# bldc-robot-main-mbed.net
KiCad netlist of a schematic drawn in Altium Designer
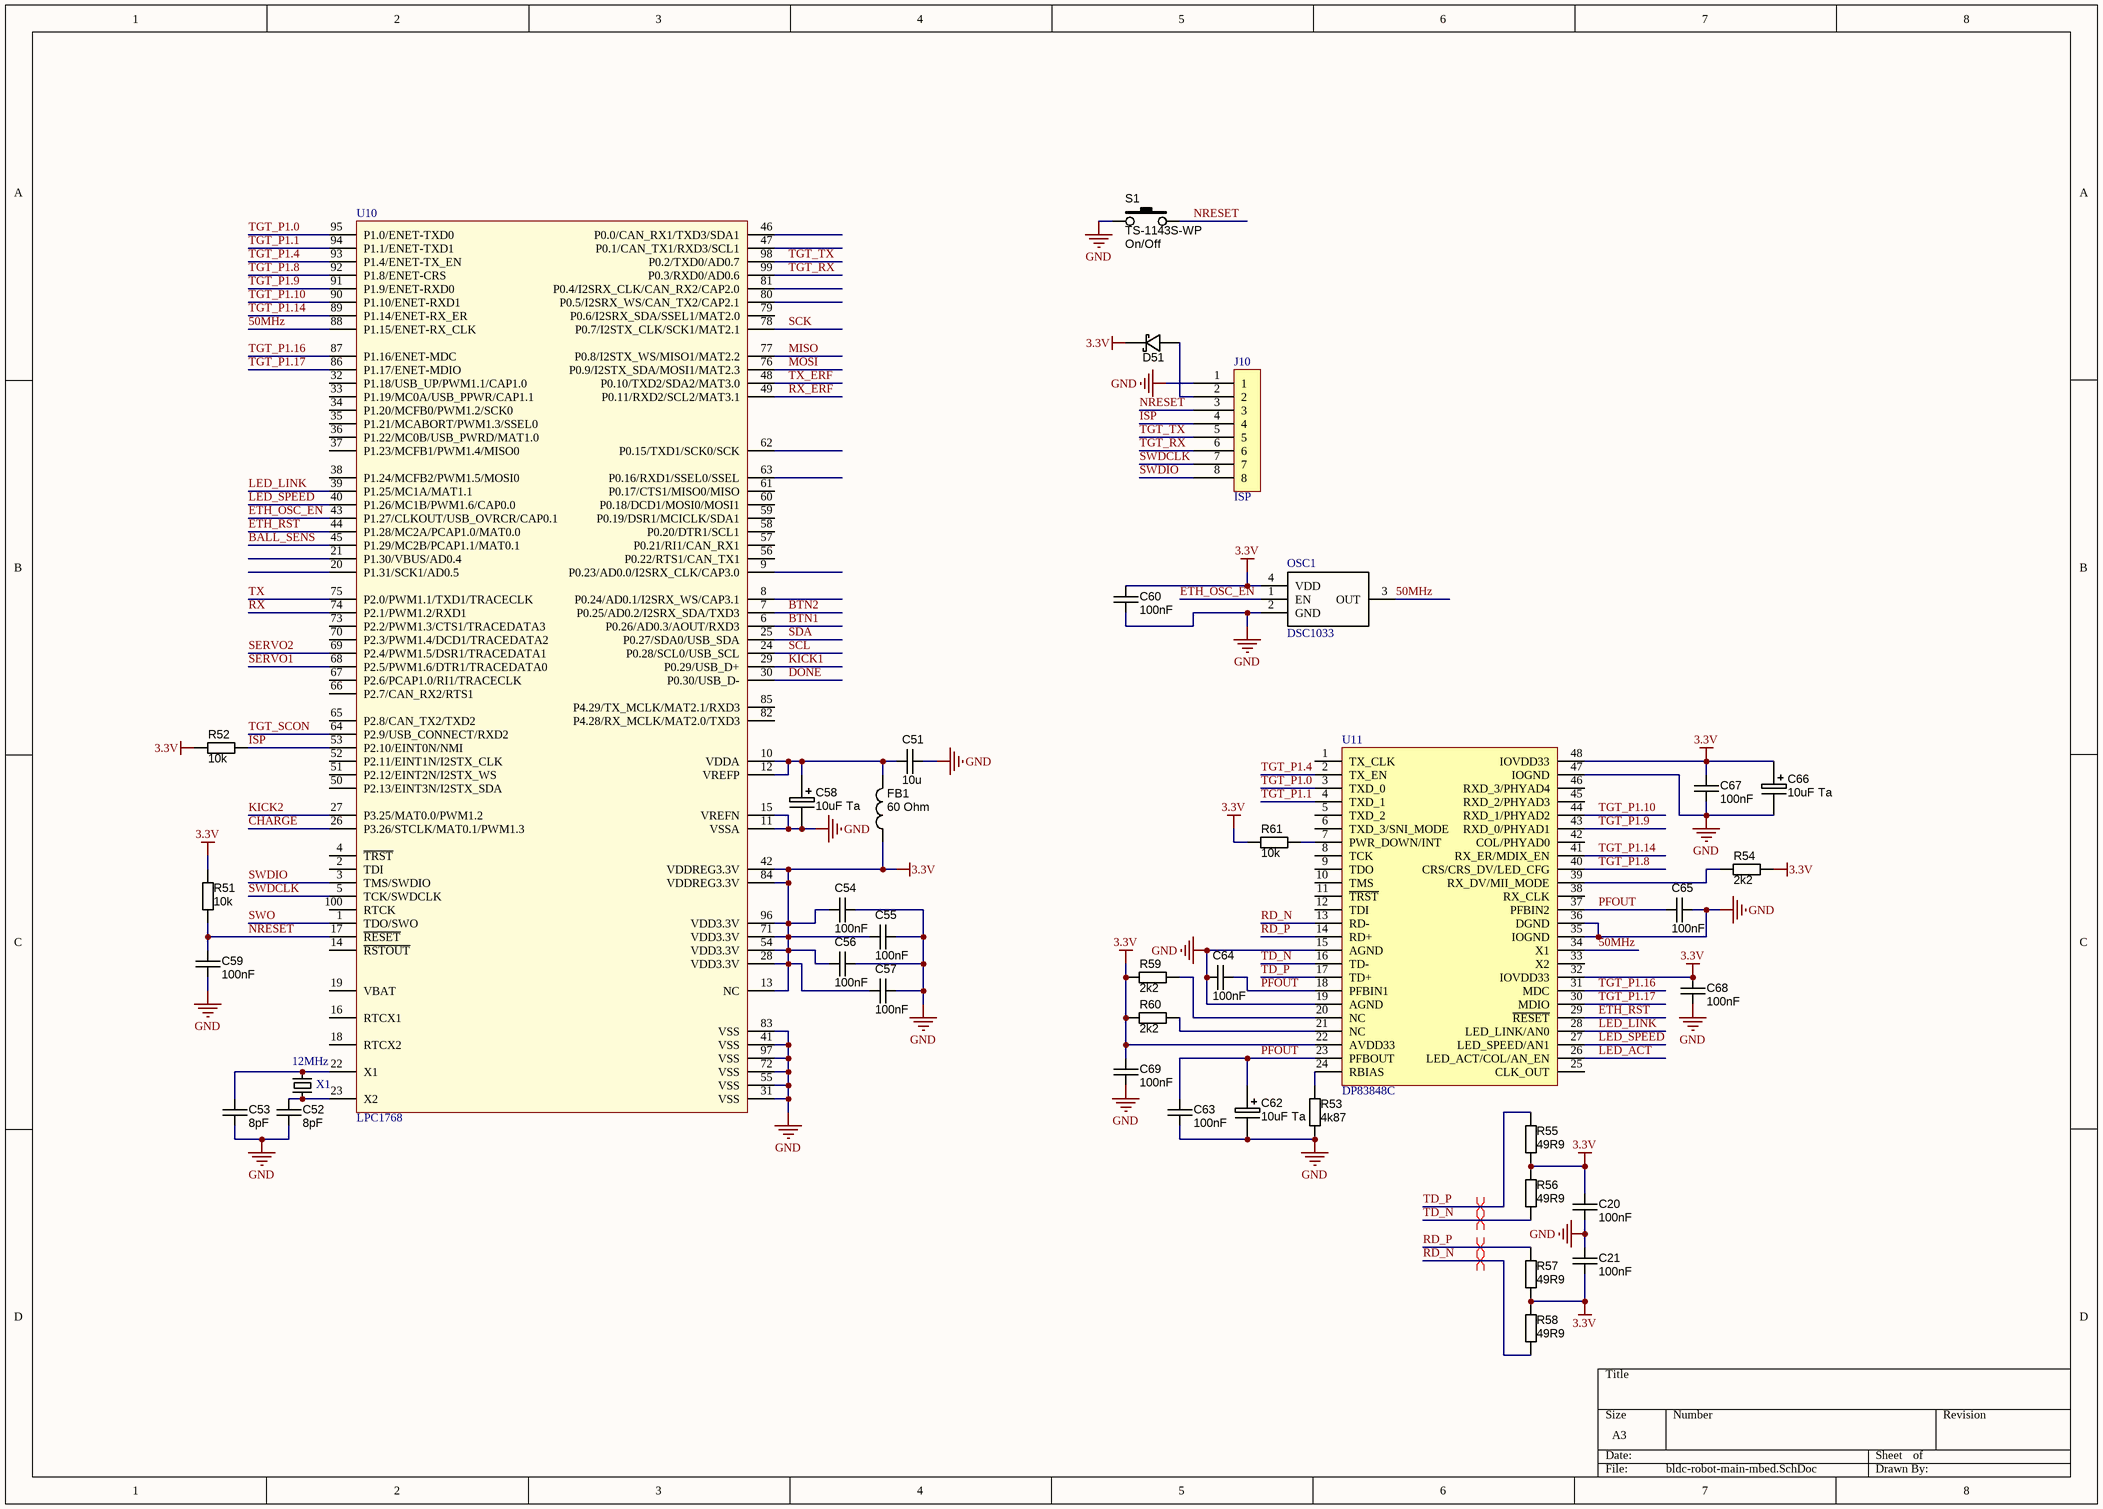
[diagram p0: bldc-robot-main-mbed.SchDoc]

(export (version "E")
  (design (tool "Eeschema 10.0.6"))
  (components
    (comp (ref "C20")
      (value "100nF")
      (footprint "CAPC1608X90N")
      (description "Capacitor SMD Cer 18pF 2% 100V NP0 0603")
      (fields (field (name "TOLERANCE") "±2%"))
      (libsource (lib "PBL - Capacitors") (part "CAPC_18p_0603_100V"))
    )
    (comp (ref "C21")
      (value "100nF")
      (footprint "CAPC1608X90N")
      (description "Capacitor SMD Cer 18pF 2% 100V NP0 0603")
      (fields (field (name "TOLERANCE") "±2%"))
      (libsource (lib "PBL - Capacitors") (part "CAPC_18p_0603_100V"))
    )
    (comp (ref "C51")
      (value "10u")
      (footprint "CAPC2012X135N")
      (description "Capacitor SMD Cer 10uF 10% 10V X5R 0805")
      (fields (field (name "TOLERANCE") "±10%"))
      (libsource (lib "PBL - Capacitors") (part "CAPC_10u_0805_10V"))
    )
    (comp (ref "C52")
      (value "8pF")
      (footprint "CAPC1608X90N")
      (description "Capacitor SMD Cer 18pF 2% 100V NP0 0603")
      (fields (field (name "TOLERANCE") "±2%"))
      (libsource (lib "PBL - Capacitors") (part "CAPC_18p_0603_100V"))
    )
    (comp (ref "C53")
      (value "8pF")
      (footprint "CAPC1608X90N")
      (description "Capacitor SMD Cer 18pF 2% 100V NP0 0603")
      (fields (field (name "TOLERANCE") "±2%"))
      (libsource (lib "PBL - Capacitors") (part "CAPC_18p_0603_100V"))
    )
    (comp (ref "C54")
      (value "100nF")
      (footprint "CAPC1608X90N")
      (description "Capacitor SMD Cer 18pF 2% 100V NP0 0603")
      (fields (field (name "TOLERANCE") "±2%"))
      (libsource (lib "PBL - Capacitors") (part "CAPC_18p_0603_100V"))
    )
    (comp (ref "C55")
      (value "100nF")
      (footprint "CAPC1608X90N")
      (description "Capacitor SMD Cer 18pF 2% 100V NP0 0603")
      (fields (field (name "TOLERANCE") "±2%"))
      (libsource (lib "PBL - Capacitors") (part "CAPC_18p_0603_100V"))
    )
    (comp (ref "C56")
      (value "100nF")
      (footprint "CAPC1608X90N")
      (description "Capacitor SMD Cer 18pF 2% 100V NP0 0603")
      (fields (field (name "TOLERANCE") "±2%"))
      (libsource (lib "PBL - Capacitors") (part "CAPC_18p_0603_100V"))
    )
    (comp (ref "C57")
      (value "100nF")
      (footprint "CAPC1608X90N")
      (description "Capacitor SMD Cer 18pF 2% 100V NP0 0603")
      (fields (field (name "TOLERANCE") "±2%"))
      (libsource (lib "PBL - Capacitors") (part "CAPC_18p_0603_100V"))
    )
    (comp (ref "C58")
      (value "10uF Ta")
      (footprint "CAPMP3528X210N")
      (description "Capacitor SMD Tantalum 47uF 20% 6.3V 1210")
      (fields (field (name "TOLERANCE") "±20%"))
      (libsource (lib "PBL - Capacitors") (part "CAPT_47u_1210_6V3"))
    )
    (comp (ref "C59")
      (value "100nF")
      (footprint "CAPC1608X90N")
      (description "Capacitor SMD Cer 18pF 2% 100V NP0 0603")
      (fields (field (name "TOLERANCE") "±2%"))
      (libsource (lib "PBL - Capacitors") (part "CAPC_18p_0603_100V"))
    )
    (comp (ref "C60")
      (value "100nF")
      (footprint "CAPC1608X90N")
      (description "Capacitor SMD Cer 18pF 2% 100V NP0 0603")
      (fields (field (name "TOLERANCE") "±2%"))
      (libsource (lib "PBL - Capacitors") (part "CAPC_18p_0603_100V"))
    )
    (comp (ref "C62")
      (value "10uF Ta")
      (footprint "CAPMP3528X210N")
      (description "Capacitor SMD Tantalum 47uF 20% 6.3V 1210")
      (fields (field (name "TOLERANCE") "±20%"))
      (libsource (lib "PBL - Capacitors") (part "CAPT_47u_1210_6V3"))
    )
    (comp (ref "C63")
      (value "100nF")
      (footprint "CAPC1608X90N")
      (description "Capacitor SMD Cer 18pF 2% 100V NP0 0603")
      (fields (field (name "TOLERANCE") "±2%"))
      (libsource (lib "PBL - Capacitors") (part "CAPC_18p_0603_100V"))
    )
    (comp (ref "C64")
      (value "100nF")
      (footprint "CAPC1608X90N")
      (description "Capacitor SMD Cer 18pF 2% 100V NP0 0603")
      (fields (field (name "TOLERANCE") "±2%"))
      (libsource (lib "PBL - Capacitors") (part "CAPC_18p_0603_100V"))
    )
    (comp (ref "C65")
      (value "100nF")
      (footprint "CAPC1608X90N")
      (description "Capacitor SMD Cer 18pF 2% 100V NP0 0603")
      (fields (field (name "TOLERANCE") "±2%"))
      (libsource (lib "PBL - Capacitors") (part "CAPC_18p_0603_100V"))
    )
    (comp (ref "C66")
      (value "10uF Ta")
      (footprint "CAPMP3528X210N")
      (description "Capacitor SMD Tantalum 47uF 20% 6.3V 1210")
      (fields (field (name "TOLERANCE") "±20%"))
      (libsource (lib "PBL - Capacitors") (part "CAPT_47u_1210_6V3"))
    )
    (comp (ref "C67")
      (value "100nF")
      (footprint "CAPC1608X90N")
      (description "Capacitor SMD Cer 18pF 2% 100V NP0 0603")
      (fields (field (name "TOLERANCE") "±2%"))
      (libsource (lib "PBL - Capacitors") (part "CAPC_18p_0603_100V"))
    )
    (comp (ref "C68")
      (value "100nF")
      (footprint "CAPC1608X90N")
      (description "Capacitor SMD Cer 18pF 2% 100V NP0 0603")
      (fields (field (name "TOLERANCE") "±2%"))
      (libsource (lib "PBL - Capacitors") (part "CAPC_18p_0603_100V"))
    )
    (comp (ref "C69")
      (value "100nF")
      (footprint "CAPC1608X90N")
      (description "Capacitor SMD Cer 18pF 2% 100V NP0 0603")
      (fields (field (name "TOLERANCE") "±2%"))
      (libsource (lib "PBL - Capacitors") (part "CAPC_18p_0603_100V"))
    )
    (comp (ref "D51")
      (value "~")
      (footprint "SOD323")
      (description "Diode Schottky SMD 20V 0.5A SOD123")
      (libsource (lib "PBL - Diodes") (part "DIODE_SCHOTTKY_SS0520"))
    )
    (comp (ref "FB1")
      (value "60 Ohm")
      (footprint "INDC1608N")
      (description "Ferrite bead 120 Ohm at 100 MHz 2A 0603 SMD")
      (libsource (lib "PBL - Inductors") (part "FERRITE_120R-100MHz_0603"))
    )
    (comp (ref "J10")
      (value "ISP")
      (footprint "MICRO-MATCH-8")
      (libsource (lib "connectors") (part "HEADER-8"))
    )
    (comp (ref "OSC1")
      (value "DSC1033")
      (footprint "DSC1033-3.2x2.5")
      (libsource (lib "misc") (part "DSC1033"))
    )
    (comp (ref "R51")
      (value "10k")
      (footprint "RESC1608X55N")
      (description "Resistor SMD chip 10k Ohm 0.1W 5% 0603")
      (fields (field (name "TOLERANCE") "±5%"))
      (libsource (lib "PBL - Resistors") (part "RES_10K_0603_5%"))
    )
    (comp (ref "R52")
      (value "10k")
      (footprint "RESC1608X55N")
      (description "Resistor SMD chip 10k Ohm 0.1W 5% 0603")
      (fields (field (name "TOLERANCE") "±5%"))
      (libsource (lib "") (part "RES_10K_0603_5%_1"))
    )
    (comp (ref "R53")
      (value "4k87")
      (footprint "RESC1608X55N")
      (description "Resistor SMD chip 10k Ohm 0.1W 5% 0603")
      (fields (field (name "TOLERANCE") "±5%"))
      (libsource (lib "PBL - Resistors") (part "RES_10K_0603_5%"))
    )
    (comp (ref "R54")
      (value "2k2")
      (footprint "RESC1608X55N")
      (description "Resistor SMD chip 10k Ohm 0.1W 5% 0603")
      (fields (field (name "TOLERANCE") "±5%"))
      (libsource (lib "") (part "RES_10K_0603_5%_1"))
    )
    (comp (ref "R55")
      (value "49R9")
      (footprint "RESC1608X55N")
      (description "Resistor SMD chip 10k Ohm 0.1W 5% 0603")
      (fields (field (name "TOLERANCE") "±5%"))
      (libsource (lib "PBL - Resistors") (part "RES_10K_0603_5%"))
    )
    (comp (ref "R56")
      (value "49R9")
      (footprint "RESC1608X55N")
      (description "Resistor SMD chip 10k Ohm 0.1W 5% 0603")
      (fields (field (name "TOLERANCE") "±5%"))
      (libsource (lib "PBL - Resistors") (part "RES_10K_0603_5%"))
    )
    (comp (ref "R57")
      (value "49R9")
      (footprint "RESC1608X55N")
      (description "Resistor SMD chip 10k Ohm 0.1W 5% 0603")
      (fields (field (name "TOLERANCE") "±5%"))
      (libsource (lib "PBL - Resistors") (part "RES_10K_0603_5%"))
    )
    (comp (ref "R58")
      (value "49R9")
      (footprint "RESC1608X55N")
      (description "Resistor SMD chip 10k Ohm 0.1W 5% 0603")
      (fields (field (name "TOLERANCE") "±5%"))
      (libsource (lib "PBL - Resistors") (part "RES_10K_0603_5%"))
    )
    (comp (ref "R59")
      (value "2k2")
      (footprint "RESC1608X55N")
      (description "Resistor SMD chip 10k Ohm 0.1W 5% 0603")
      (fields (field (name "TOLERANCE") "±5%"))
      (libsource (lib "") (part "RES_10K_0603_5%_1"))
    )
    (comp (ref "R60")
      (value "2k2")
      (footprint "RESC1608X55N")
      (description "Resistor SMD chip 10k Ohm 0.1W 5% 0603")
      (fields (field (name "TOLERANCE") "±5%"))
      (libsource (lib "") (part "RES_10K_0603_5%_1"))
    )
    (comp (ref "R61")
      (value "10k")
      (footprint "RESC1608X55N")
      (description "Resistor SMD chip 10k Ohm 0.1W 5% 0603")
      (fields (field (name "TOLERANCE") "±5%"))
      (libsource (lib "") (part "RES_10K_0603_5%_1"))
    )
    (comp (ref "S1")
      (value "TS-1143S-WP")
      (footprint "TS-1143S")
      (description "Switch SMD Tact 4.3mm Stem")
      (fields (field (name "FUNCTION") "On/Off"))
      (libsource (lib "PBL - Switches") (part "SW_SMD_PB_4.3mm"))
    )
    (comp (ref "U10") (value "LPC1768") (footprint "LQFP100") (libsource (lib "nxp") (part "LPC1768")))
    (comp (ref "U11")
      (value "DP83848C")
      (footprint "PQFP48")
      (libsource (lib "texas_instruments") (part "DP83848C"))
    )
    (comp (ref "X1")
      (value "12MHz")
      (footprint "XTAL-3.2x2.5")
      (libsource (lib "misc") (part "XTAL-3.2X2.5"))
    )
  )
  (nets
    (net (code "1") (name "/50MHz") (class "Default")
      (node (ref "OSC1") (pin "3") (pinfunction "OUT_3") (pintype "passive"))
      (node (ref "U10") (pin "88") (pinfunction "P1.15/ENET-RX_CLK_88") (pintype "passive"))
      (node (ref "U11") (pin "34") (pinfunction "X1_34") (pintype "passive"))
    )
    (net (code "2") (name "/BALL_SENS") (class "Default")
      (node (ref "U10") (pin "45") (pinfunction "P1.29/MC2B/PCAP1.1/MAT0.1_45") (pintype "passive"))
    )
    (net (code "3") (name "/BTN1") (class "Default")
      (node (ref "U10") (pin "6") (pinfunction "P0.26/AD0.3/AOUT/RXD3_6") (pintype "passive"))
    )
    (net (code "4") (name "/BTN2") (class "Default")
      (node (ref "U10") (pin "7") (pinfunction "P0.25/AD0.2/I2SRX_SDA/TXD3_7") (pintype "passive"))
    )
    (net (code "5") (name "/CHARGE") (class "Default")
      (node (ref "U10") (pin "26") (pinfunction "P3.26/STCLK/MAT0.1/PWM1.3_26") (pintype "passive"))
    )
    (net (code "6") (name "/DONE") (class "Default")
      (node (ref "U10") (pin "30") (pinfunction "P0.30/USB_D-_30") (pintype "passive"))
    )
    (net (code "7") (name "/ETH_OSC_EN") (class "Default")
      (node (ref "OSC1") (pin "1") (pinfunction "EN_1") (pintype "passive"))
      (node (ref "U10") (pin "43") (pinfunction "P1.27/CLKOUT/USB_OVRCR/CAP0.1_43") (pintype "passive"))
    )
    (net (code "8") (name "/ETH_RST") (class "Default")
      (node (ref "U10") (pin "44") (pinfunction "P1.28/MC2A/PCAP1.0/MAT0.0_44") (pintype "passive"))
      (node (ref "U11") (pin "29") (pinfunction "~{RESET}_29") (pintype "passive"))
    )
    (net (code "9") (name "/ISP") (class "Default")
      (node (ref "J10") (pin "4") (pinfunction "4_4") (pintype "passive"))
      (node (ref "R52") (pin "1") (pinfunction "1_1") (pintype "passive"))
      (node (ref "U10") (pin "53") (pinfunction "P2.10/EINT0N/NMI_53") (pintype "passive"))
    )
    (net (code "10") (name "/KICK1") (class "Default")
      (node (ref "U10") (pin "29") (pinfunction "P0.29/USB_D+_29") (pintype "passive"))
    )
    (net (code "11") (name "/KICK2") (class "Default")
      (node (ref "U10") (pin "27") (pinfunction "P3.25/MAT0.0/PWM1.2_27") (pintype "passive"))
    )
    (net (code "12") (name "/LED_ACT") (class "Default")
      (node (ref "U11") (pin "26") (pinfunction "LED_ACT/COL/AN_EN_26") (pintype "passive"))
    )
    (net (code "13") (name "/LED_LINK") (class "Default")
      (node (ref "U10") (pin "39") (pinfunction "P1.25/MC1A/MAT1.1_39") (pintype "passive"))
      (node (ref "U11") (pin "28") (pinfunction "LED_LINK/AN0_28") (pintype "passive"))
    )
    (net (code "14") (name "/LED_SPEED") (class "Default")
      (node (ref "U10") (pin "40") (pinfunction "P1.26/MC1B/PWM1.6/CAP0.0_40") (pintype "passive"))
      (node (ref "U11") (pin "27") (pinfunction "LED_SPEED/AN1_27") (pintype "passive"))
    )
    (net (code "15") (name "/MISO") (class "Default")
      (node (ref "U10") (pin "77") (pinfunction "P0.8/I2STX_WS/MISO1/MAT2.2_77") (pintype "passive"))
    )
    (net (code "16") (name "/MOSI") (class "Default")
      (node (ref "U10") (pin "76") (pinfunction "P0.9/I2STX_SDA/MOSI1/MAT2.3_76") (pintype "passive"))
    )
    (net (code "17") (name "/NRESET") (class "Default")
      (node (ref "C59") (pin "1") (pintype "passive"))
      (node (ref "J10") (pin "3") (pinfunction "3_3") (pintype "passive"))
      (node (ref "R51") (pin "2") (pinfunction "2_2") (pintype "passive"))
      (node (ref "S1") (pin "2") (pintype "passive"))
      (node (ref "U10") (pin "17") (pinfunction "~{RESET}_17") (pintype "passive"))
    )
    (net (code "18") (name "/PFOUT") (class "Default")
      (node (ref "C62") (pin "1") (pintype "passive"))
      (node (ref "C63") (pin "2") (pintype "passive"))
      (node (ref "C64") (pin "2") (pintype "passive"))
      (node (ref "C65") (pin "1") (pintype "passive"))
      (node (ref "U11") (pin "18") (pinfunction "PFBIN1_18") (pintype "passive"))
      (node (ref "U11") (pin "23") (pinfunction "PFBOUT_23") (pintype "passive"))
      (node (ref "U11") (pin "37") (pinfunction "PFBIN2_37") (pintype "passive"))
    )
    (net (code "19") (name "/RD_N") (class "Default")
      (node (ref "R58") (pin "2") (pinfunction "2_2") (pintype "passive"))
      (node (ref "U11") (pin "13") (pinfunction "RD-_13") (pintype "passive"))
    )
    (net (code "20") (name "/RD_P") (class "Default")
      (node (ref "R57") (pin "1") (pinfunction "1_1") (pintype "passive"))
      (node (ref "U11") (pin "14") (pinfunction "RD+_14") (pintype "passive"))
    )
    (net (code "21") (name "/RX") (class "Default")
      (node (ref "U10") (pin "74") (pinfunction "P2.1/PWM1.2/RXD1_74") (pintype "passive"))
    )
    (net (code "22") (name "/RX_ERF") (class "Default")
      (node (ref "U10") (pin "49") (pinfunction "P0.11/RXD2/SCL2/MAT3.1_49") (pintype "passive"))
    )
    (net (code "23") (name "/SCK") (class "Default")
      (node (ref "U10") (pin "78") (pinfunction "P0.7/I2STX_CLK/SCK1/MAT2.1_78") (pintype "passive"))
    )
    (net (code "24") (name "/SCL") (class "Default")
      (node (ref "U10") (pin "24") (pinfunction "P0.28/SCL0/USB_SCL_24") (pintype "passive"))
    )
    (net (code "25") (name "/SDA") (class "Default")
      (node (ref "U10") (pin "25") (pinfunction "P0.27/SDA0/USB_SDA_25") (pintype "passive"))
    )
    (net (code "26") (name "/SERVO1") (class "Default")
      (node (ref "U10") (pin "68") (pinfunction "P2.5/PWM1.6/DTR1/TRACEDATA0_68") (pintype "passive"))
    )
    (net (code "27") (name "/SERVO2") (class "Default")
      (node (ref "U10") (pin "69") (pinfunction "P2.4/PWM1.5/DSR1/TRACEDATA1_69") (pintype "passive"))
    )
    (net (code "28") (name "/SWDCLK") (class "Default")
      (node (ref "J10") (pin "7") (pinfunction "7_7") (pintype "passive"))
      (node (ref "U10") (pin "5") (pinfunction "TCK/SWDCLK_5") (pintype "passive"))
    )
    (net (code "29") (name "/SWDIO") (class "Default")
      (node (ref "J10") (pin "8") (pinfunction "8_8") (pintype "passive"))
      (node (ref "U10") (pin "3") (pinfunction "TMS/SWDIO_3") (pintype "passive"))
    )
    (net (code "30") (name "/SWO") (class "Default")
      (node (ref "U10") (pin "1") (pinfunction "TDO/SWO_1") (pintype "passive"))
    )
    (net (code "31") (name "/TD_N") (class "Default")
      (node (ref "R56") (pin "2") (pinfunction "2_2") (pintype "passive"))
      (node (ref "U11") (pin "16") (pinfunction "TD-_16") (pintype "passive"))
    )
    (net (code "32") (name "/TD_P") (class "Default")
      (node (ref "R55") (pin "1") (pinfunction "1_1") (pintype "passive"))
      (node (ref "U11") (pin "17") (pinfunction "TD+_17") (pintype "passive"))
    )
    (net (code "33") (name "/TGT_P1.0") (class "Default")
      (node (ref "U10") (pin "95") (pinfunction "P1.0/ENET-TXD0_95") (pintype "passive"))
      (node (ref "U11") (pin "3") (pinfunction "TXD_0_3") (pintype "passive"))
    )
    (net (code "34") (name "/TGT_P1.1") (class "Default")
      (node (ref "U10") (pin "94") (pinfunction "P1.1/ENET-TXD1_94") (pintype "passive"))
      (node (ref "U11") (pin "4") (pinfunction "TXD_1_4") (pintype "passive"))
    )
    (net (code "35") (name "/TGT_P1.4") (class "Default")
      (node (ref "U10") (pin "93") (pinfunction "P1.4/ENET-TX_EN_93") (pintype "passive"))
      (node (ref "U11") (pin "2") (pinfunction "TX_EN_2") (pintype "passive"))
    )
    (net (code "36") (name "/TGT_P1.8") (class "Default")
      (node (ref "U10") (pin "92") (pinfunction "P1.8/ENET-CRS_92") (pintype "passive"))
      (node (ref "U11") (pin "40") (pinfunction "CRS/CRS_DV/LED_CFG_40") (pintype "passive"))
    )
    (net (code "37") (name "/TGT_P1.9") (class "Default")
      (node (ref "U10") (pin "91") (pinfunction "P1.9/ENET-RXD0_91") (pintype "passive"))
      (node (ref "U11") (pin "43") (pinfunction "RXD_0/PHYAD1_43") (pintype "passive"))
    )
    (net (code "38") (name "/TGT_P1.10") (class "Default")
      (node (ref "U10") (pin "90") (pinfunction "P1.10/ENET-RXD1_90") (pintype "passive"))
      (node (ref "U11") (pin "44") (pinfunction "RXD_1/PHYAD2_44") (pintype "passive"))
    )
    (net (code "39") (name "/TGT_P1.14") (class "Default")
      (node (ref "U10") (pin "89") (pinfunction "P1.14/ENET-RX_ER_89") (pintype "passive"))
      (node (ref "U11") (pin "41") (pinfunction "RX_ER/MDIX_EN_41") (pintype "passive"))
    )
    (net (code "40") (name "/TGT_P1.16") (class "Default")
      (node (ref "U10") (pin "87") (pinfunction "P1.16/ENET-MDC_87") (pintype "passive"))
      (node (ref "U11") (pin "31") (pinfunction "MDC_31") (pintype "passive"))
    )
    (net (code "41") (name "/TGT_P1.17") (class "Default")
      (node (ref "U10") (pin "86") (pinfunction "P1.17/ENET-MDIO_86") (pintype "passive"))
      (node (ref "U11") (pin "30") (pinfunction "MDIO_30") (pintype "passive"))
    )
    (net (code "42") (name "/TGT_RX") (class "Default")
      (node (ref "J10") (pin "6") (pinfunction "6_6") (pintype "passive"))
      (node (ref "U10") (pin "99") (pinfunction "P0.3/RXD0/AD0.6_99") (pintype "passive"))
    )
    (net (code "43") (name "/TGT_SCON") (class "Default")
      (node (ref "U10") (pin "64") (pinfunction "P2.9/USB_CONNECT/RXD2_64") (pintype "passive"))
    )
    (net (code "44") (name "/TGT_TX") (class "Default")
      (node (ref "J10") (pin "5") (pinfunction "5_5") (pintype "passive"))
      (node (ref "U10") (pin "98") (pinfunction "P0.2/TXD0/AD0.7_98") (pintype "passive"))
    )
    (net (code "45") (name "/TX") (class "Default")
      (node (ref "U10") (pin "75") (pinfunction "P2.0/PWM1.1/TXD1/TRACECLK_75") (pintype "passive"))
    )
    (net (code "46") (name "/TX_ERF") (class "Default")
      (node (ref "U10") (pin "48") (pinfunction "P0.10/TXD2/SDA2/MAT3.0_48") (pintype "passive"))
    )
    (net (code "47") (name "3.3V") (class "Default")
      (node (ref "C20") (pin "2") (pintype "passive"))
      (node (ref "C21") (pin "1") (pintype "passive"))
      (node (ref "C54") (pin "1") (pintype "passive"))
      (node (ref "C55") (pin "1") (pintype "passive"))
      (node (ref "C56") (pin "1") (pintype "passive"))
      (node (ref "C57") (pin "1") (pintype "passive"))
      (node (ref "C60") (pin "2") (pintype "passive"))
      (node (ref "C66") (pin "1") (pintype "passive"))
      (node (ref "C67") (pin "2") (pintype "passive"))
      (node (ref "C68") (pin "2") (pintype "passive"))
      (node (ref "C69") (pin "2") (pintype "passive"))
      (node (ref "D51") (pin "K") (pinfunction "K_K") (pintype "passive"))
      (node (ref "FB1") (pin "1") (pinfunction "1_1") (pintype "passive"))
      (node (ref "OSC1") (pin "4") (pinfunction "VDD_4") (pintype "passive"))
      (node (ref "R51") (pin "1") (pinfunction "1_1") (pintype "passive"))
      (node (ref "R52") (pin "2") (pinfunction "2_2") (pintype "passive"))
      (node (ref "R54") (pin "1") (pinfunction "1_1") (pintype "passive"))
      (node (ref "R55") (pin "2") (pinfunction "2_2") (pintype "passive"))
      (node (ref "R56") (pin "1") (pinfunction "1_1") (pintype "passive"))
      (node (ref "R57") (pin "2") (pinfunction "2_2") (pintype "passive"))
      (node (ref "R58") (pin "1") (pinfunction "1_1") (pintype "passive"))
      (node (ref "R59") (pin "2") (pinfunction "2_2") (pintype "passive"))
      (node (ref "R60") (pin "2") (pinfunction "2_2") (pintype "passive"))
      (node (ref "R61") (pin "2") (pinfunction "2_2") (pintype "passive"))
      (node (ref "U10") (pin "13") (pinfunction "NC_13") (pintype "passive"))
      (node (ref "U10") (pin "28") (pinfunction "VDD3.3V_28") (pintype "passive"))
      (node (ref "U10") (pin "42") (pinfunction "VDDREG3.3V_42") (pintype "passive"))
      (node (ref "U10") (pin "54") (pinfunction "VDD3.3V_54") (pintype "passive"))
      (node (ref "U10") (pin "71") (pinfunction "VDD3.3V_71") (pintype "passive"))
      (node (ref "U10") (pin "84") (pinfunction "VDDREG3.3V_84") (pintype "passive"))
      (node (ref "U10") (pin "96") (pinfunction "VDD3.3V_96") (pintype "passive"))
      (node (ref "U11") (pin "22") (pinfunction "AVDD33_22") (pintype "passive"))
      (node (ref "U11") (pin "32") (pinfunction "IOVDD33_32") (pintype "passive"))
      (node (ref "U11") (pin "48") (pinfunction "IOVDD33_48") (pintype "passive"))
    )
    (net (code "48") (name "GND") (class "Default")
      (node (ref "C20") (pin "1") (pintype "passive"))
      (node (ref "C21") (pin "2") (pintype "passive"))
      (node (ref "C51") (pin "2") (pintype "passive"))
      (node (ref "C52") (pin "2") (pintype "passive"))
      (node (ref "C53") (pin "2") (pintype "passive"))
      (node (ref "C54") (pin "2") (pintype "passive"))
      (node (ref "C55") (pin "2") (pintype "passive"))
      (node (ref "C56") (pin "2") (pintype "passive"))
      (node (ref "C57") (pin "2") (pintype "passive"))
      (node (ref "C58") (pin "2") (pintype "passive"))
      (node (ref "C59") (pin "2") (pintype "passive"))
      (node (ref "C60") (pin "1") (pintype "passive"))
      (node (ref "C62") (pin "2") (pintype "passive"))
      (node (ref "C63") (pin "1") (pintype "passive"))
      (node (ref "C64") (pin "1") (pintype "passive"))
      (node (ref "C65") (pin "2") (pintype "passive"))
      (node (ref "C66") (pin "2") (pintype "passive"))
      (node (ref "C67") (pin "1") (pintype "passive"))
      (node (ref "C68") (pin "1") (pintype "passive"))
      (node (ref "C69") (pin "1") (pintype "passive"))
      (node (ref "J10") (pin "1") (pinfunction "1_1") (pintype "passive"))
      (node (ref "OSC1") (pin "2") (pinfunction "GND_2") (pintype "passive"))
      (node (ref "R53") (pin "2") (pinfunction "2_2") (pintype "passive"))
      (node (ref "S1") (pin "1") (pintype "passive"))
      (node (ref "U10") (pin "11") (pinfunction "VSSA_11") (pintype "passive"))
      (node (ref "U10") (pin "15") (pinfunction "VREFN_15") (pintype "passive"))
      (node (ref "U10") (pin "31") (pinfunction "VSS_31") (pintype "passive"))
      (node (ref "U10") (pin "41") (pinfunction "VSS_41") (pintype "passive"))
      (node (ref "U10") (pin "55") (pinfunction "VSS_55") (pintype "passive"))
      (node (ref "U10") (pin "72") (pinfunction "VSS_72") (pintype "passive"))
      (node (ref "U10") (pin "83") (pinfunction "VSS_83") (pintype "passive"))
      (node (ref "U10") (pin "97") (pinfunction "VSS_97") (pintype "passive"))
      (node (ref "U11") (pin "15") (pinfunction "AGND_15") (pintype "passive"))
      (node (ref "U11") (pin "19") (pinfunction "AGND_19") (pintype "passive"))
      (node (ref "U11") (pin "35") (pinfunction "IOGND_35") (pintype "passive"))
      (node (ref "U11") (pin "36") (pinfunction "DGND_36") (pintype "passive"))
      (node (ref "U11") (pin "47") (pinfunction "IOGND_47") (pintype "passive"))
    )
    (net (code "49") (name "Net-(D51-PadA)") (class "Default")
      (node (ref "D51") (pin "A") (pinfunction "A_A") (pintype "passive"))
      (node (ref "J10") (pin "2") (pinfunction "2_2") (pintype "passive"))
    )
    (net (code "50") (name "Net-(R59-Pad1)") (class "Default")
      (node (ref "R59") (pin "1") (pinfunction "1_1") (pintype "passive"))
      (node (ref "U11") (pin "20") (pinfunction "NC_20") (pintype "passive"))
    )
    (net (code "51") (name "Net-(R60-Pad1)") (class "Default")
      (node (ref "R60") (pin "1") (pinfunction "1_1") (pintype "passive"))
      (node (ref "U11") (pin "21") (pinfunction "NC_21") (pintype "passive"))
    )
    (net (code "52") (name "Net-(U10-VDDA)") (class "Default")
      (node (ref "C51") (pin "1") (pintype "passive"))
      (node (ref "C58") (pin "1") (pintype "passive"))
      (node (ref "FB1") (pin "2") (pinfunction "2_2") (pintype "passive"))
      (node (ref "U10") (pin "10") (pinfunction "VDDA_10") (pintype "passive"))
      (node (ref "U10") (pin "12") (pinfunction "VREFP_12") (pintype "passive"))
    )
    (net (code "53") (name "Net-(U10-X1)") (class "Default")
      (node (ref "C53") (pin "1") (pintype "passive"))
      (node (ref "U10") (pin "22") (pinfunction "X1_22") (pintype "passive"))
      (node (ref "X1") (pin "3") (pinfunction "3_3") (pintype "passive"))
    )
    (net (code "54") (name "Net-(U10-X2)") (class "Default")
      (node (ref "C52") (pin "1") (pintype "passive"))
      (node (ref "U10") (pin "23") (pinfunction "X2_23") (pintype "passive"))
      (node (ref "X1") (pin "1") (pinfunction "1_1") (pintype "passive"))
    )
    (net (code "55") (name "Net-(U11-PWR_DOWN{slash}INT)") (class "Default")
      (node (ref "R61") (pin "1") (pinfunction "1_1") (pintype "passive"))
      (node (ref "U11") (pin "7") (pinfunction "PWR_DOWN/INT_7") (pintype "passive"))
    )
    (net (code "56") (name "Net-(U11-RBIAS)") (class "Default")
      (node (ref "R53") (pin "1") (pinfunction "1_1") (pintype "passive"))
      (node (ref "U11") (pin "24") (pinfunction "RBIAS_24") (pintype "passive"))
    )
    (net (code "57") (name "Net-(U11-RX_DV{slash}MII_MODE)") (class "Default")
      (node (ref "R54") (pin "2") (pinfunction "2_2") (pintype "passive"))
      (node (ref "U11") (pin "39") (pinfunction "RX_DV/MII_MODE_39") (pintype "passive"))
    )
    (net (code "58") (name "unconnected-(U10-P0.0{slash}CAN_RX1{slash}TXD3{slash}SDA1-Pad46)") (class "Default")
      (node (ref "U10") (pin "46") (pinfunction "P0.0/CAN_RX1/TXD3/SDA1_46") (pintype "passive"))
    )
    (net (code "59") (name "unconnected-(U10-P0.1{slash}CAN_TX1{slash}RXD3{slash}SCL1-Pad47)") (class "Default")
      (node (ref "U10") (pin "47") (pinfunction "P0.1/CAN_TX1/RXD3/SCL1_47") (pintype "passive"))
    )
    (net (code "60") (name "unconnected-(U10-P0.4{slash}I2SRX_CLK{slash}CAN_RX2{slash}CAP2.0-Pad81)") (class "Default")
      (node (ref "U10") (pin "81") (pinfunction "P0.4/I2SRX_CLK/CAN_RX2/CAP2.0_81") (pintype "passive"))
    )
    (net (code "61") (name "unconnected-(U10-P0.5{slash}I2SRX_WS{slash}CAN_TX2{slash}CAP2.1-Pad80)") (class "Default")
      (node (ref "U10") (pin "80") (pinfunction "P0.5/I2SRX_WS/CAN_TX2/CAP2.1_80") (pintype "passive"))
    )
    (net (code "62") (name "unconnected-(U10-P0.6{slash}I2SRX_SDA{slash}SSEL1{slash}MAT2.0-Pad79)") (class "Default")
      (node (ref "U10") (pin "79") (pinfunction "P0.6/I2SRX_SDA/SSEL1/MAT2.0_79") (pintype "passive"))
    )
    (net (code "63") (name "unconnected-(U10-P0.15{slash}TXD1{slash}SCK0{slash}SCK-Pad62)") (class "Default")
      (node (ref "U10") (pin "62") (pinfunction "P0.15/TXD1/SCK0/SCK_62") (pintype "passive"))
    )
    (net (code "64") (name "unconnected-(U10-P0.16{slash}RXD1{slash}SSEL0{slash}SSEL-Pad63)") (class "Default")
      (node (ref "U10") (pin "63") (pinfunction "P0.16/RXD1/SSEL0/SSEL_63") (pintype "passive"))
    )
    (net (code "65") (name "unconnected-(U10-P0.17{slash}CTS1{slash}MISO0{slash}MISO-Pad61)") (class "Default")
      (node (ref "U10") (pin "61") (pinfunction "P0.17/CTS1/MISO0/MISO_61") (pintype "passive"))
    )
    (net (code "66") (name "unconnected-(U10-P0.18{slash}DCD1{slash}MOSI0{slash}MOSI1-Pad60)") (class "Default")
      (node (ref "U10") (pin "60") (pinfunction "P0.18/DCD1/MOSI0/MOSI1_60") (pintype "passive"))
    )
    (net (code "67") (name "unconnected-(U10-P0.19{slash}DSR1{slash}MCICLK{slash}SDA1-Pad59)") (class "Default")
      (node (ref "U10") (pin "59") (pinfunction "P0.19/DSR1/MCICLK/SDA1_59") (pintype "passive"))
    )
    (net (code "68") (name "unconnected-(U10-P0.20{slash}DTR1{slash}SCL1-Pad58)") (class "Default")
      (node (ref "U10") (pin "58") (pinfunction "P0.20/DTR1/SCL1_58") (pintype "passive"))
    )
    (net (code "69") (name "unconnected-(U10-P0.21{slash}RI1{slash}CAN_RX1-Pad57)") (class "Default")
      (node (ref "U10") (pin "57") (pinfunction "P0.21/RI1/CAN_RX1_57") (pintype "passive"))
    )
    (net (code "70") (name "unconnected-(U10-P0.22{slash}RTS1{slash}CAN_TX1-Pad56)") (class "Default")
      (node (ref "U10") (pin "56") (pinfunction "P0.22/RTS1/CAN_TX1_56") (pintype "passive"))
    )
    (net (code "71") (name "unconnected-(U10-P0.23{slash}AD0.0{slash}I2SRX_CLK{slash}CAP3.0-Pad9)") (class "Default")
      (node (ref "U10") (pin "9") (pinfunction "P0.23/AD0.0/I2SRX_CLK/CAP3.0_9") (pintype "passive"))
    )
    (net (code "72") (name "unconnected-(U10-P0.24{slash}AD0.1{slash}I2SRX_WS{slash}CAP3.1-Pad8)") (class "Default")
      (node (ref "U10") (pin "8") (pinfunction "P0.24/AD0.1/I2SRX_WS/CAP3.1_8") (pintype "passive"))
    )
    (net (code "73") (name "unconnected-(U10-P1.18{slash}USB_UP{slash}PWM1.1{slash}CAP1.0-Pad32)") (class "Default")
      (node (ref "U10") (pin "32") (pinfunction "P1.18/USB_UP/PWM1.1/CAP1.0_32") (pintype "passive"))
    )
    (net (code "74") (name "unconnected-(U10-P1.19{slash}MC0A{slash}USB_PPWR{slash}CAP1.1-Pad33)") (class "Default")
      (node (ref "U10") (pin "33") (pinfunction "P1.19/MC0A/USB_PPWR/CAP1.1_33") (pintype "passive"))
    )
    (net (code "75") (name "unconnected-(U10-P1.20{slash}MCFB0{slash}PWM1.2{slash}SCK0-Pad34)") (class "Default")
      (node (ref "U10") (pin "34") (pinfunction "P1.20/MCFB0/PWM1.2/SCK0_34") (pintype "passive"))
    )
    (net (code "76") (name "unconnected-(U10-P1.21{slash}MCABORT{slash}PWM1.3{slash}SSEL0-Pad35)") (class "Default")
      (node (ref "U10") (pin "35") (pinfunction "P1.21/MCABORT/PWM1.3/SSEL0_35") (pintype "passive"))
    )
    (net (code "77") (name "unconnected-(U10-P1.22{slash}MC0B{slash}USB_PWRD{slash}MAT1.0-Pad36)") (class "Default")
      (node (ref "U10") (pin "36") (pinfunction "P1.22/MC0B/USB_PWRD/MAT1.0_36") (pintype "passive"))
    )
    (net (code "78") (name "unconnected-(U10-P1.23{slash}MCFB1{slash}PWM1.4{slash}MISO0-Pad37)") (class "Default")
      (node (ref "U10") (pin "37") (pinfunction "P1.23/MCFB1/PWM1.4/MISO0_37") (pintype "passive"))
    )
    (net (code "79") (name "unconnected-(U10-P1.24{slash}MCFB2{slash}PWM1.5{slash}MOSI0-Pad38)") (class "Default")
      (node (ref "U10") (pin "38") (pinfunction "P1.24/MCFB2/PWM1.5/MOSI0_38") (pintype "passive"))
    )
    (net (code "80") (name "unconnected-(U10-P1.30{slash}VBUS{slash}AD0.4-Pad21)") (class "Default")
      (node (ref "U10") (pin "21") (pinfunction "P1.30/VBUS/AD0.4_21") (pintype "passive"))
    )
    (net (code "81") (name "unconnected-(U10-P1.31{slash}SCK1{slash}AD0.5-Pad20)") (class "Default")
      (node (ref "U10") (pin "20") (pinfunction "P1.31/SCK1/AD0.5_20") (pintype "passive"))
    )
    (net (code "82") (name "unconnected-(U10-P2.2{slash}PWM1.3{slash}CTS1{slash}TRACEDATA3-Pad73)") (class "Default")
      (node (ref "U10") (pin "73") (pinfunction "P2.2/PWM1.3/CTS1/TRACEDATA3_73") (pintype "passive"))
    )
    (net (code "83") (name "unconnected-(U10-P2.3{slash}PWM1.4{slash}DCD1{slash}TRACEDATA2-Pad70)") (class "Default")
      (node (ref "U10") (pin "70") (pinfunction "P2.3/PWM1.4/DCD1/TRACEDATA2_70") (pintype "passive"))
    )
    (net (code "84") (name "unconnected-(U10-P2.6{slash}PCAP1.0{slash}RI1{slash}TRACECLK-Pad67)") (class "Default")
      (node (ref "U10") (pin "67") (pinfunction "P2.6/PCAP1.0/RI1/TRACECLK_67") (pintype "passive"))
    )
    (net (code "85") (name "unconnected-(U10-P2.7{slash}CAN_RX2{slash}RTS1-Pad66)") (class "Default")
      (node (ref "U10") (pin "66") (pinfunction "P2.7/CAN_RX2/RTS1_66") (pintype "passive"))
    )
    (net (code "86") (name "unconnected-(U10-P2.8{slash}CAN_TX2{slash}TXD2-Pad65)") (class "Default")
      (node (ref "U10") (pin "65") (pinfunction "P2.8/CAN_TX2/TXD2_65") (pintype "passive"))
    )
    (net (code "87") (name "unconnected-(U10-P2.11{slash}EINT1N{slash}I2STX_CLK-Pad52)") (class "Default")
      (node (ref "U10") (pin "52") (pinfunction "P2.11/EINT1N/I2STX_CLK_52") (pintype "passive"))
    )
    (net (code "88") (name "unconnected-(U10-P2.12{slash}EINT2N{slash}I2STX_WS-Pad51)") (class "Default")
      (node (ref "U10") (pin "51") (pinfunction "P2.12/EINT2N/I2STX_WS_51") (pintype "passive"))
    )
    (net (code "89") (name "unconnected-(U10-P2.13{slash}EINT3N{slash}I2STX_SDA-Pad50)") (class "Default")
      (node (ref "U10") (pin "50") (pinfunction "P2.13/EINT3N/I2STX_SDA_50") (pintype "passive"))
    )
    (net (code "90") (name "unconnected-(U10-P4.28{slash}RX_MCLK{slash}MAT2.0{slash}TXD3-Pad82)") (class "Default")
      (node (ref "U10") (pin "82") (pinfunction "P4.28/RX_MCLK/MAT2.0/TXD3_82") (pintype "passive"))
    )
    (net (code "91") (name "unconnected-(U10-P4.29{slash}TX_MCLK{slash}MAT2.1{slash}RXD3-Pad85)") (class "Default")
      (node (ref "U10") (pin "85") (pinfunction "P4.29/TX_MCLK/MAT2.1/RXD3_85") (pintype "passive"))
    )
    (net (code "92") (name "unconnected-(U10-RTCK-Pad100)") (class "Default")
      (node (ref "U10") (pin "100") (pinfunction "RTCK_100") (pintype "passive"))
    )
    (net (code "93") (name "unconnected-(U10-RTCX1-Pad16)") (class "Default")
      (node (ref "U10") (pin "16") (pinfunction "RTCX1_16") (pintype "passive"))
    )
    (net (code "94") (name "unconnected-(U10-RTCX2-Pad18)") (class "Default")
      (node (ref "U10") (pin "18") (pinfunction "RTCX2_18") (pintype "passive"))
    )
    (net (code "95") (name "unconnected-(U10-TDI-Pad2)") (class "Default")
      (node (ref "U10") (pin "2") (pinfunction "TDI_2") (pintype "passive"))
    )
    (net (code "96") (name "unconnected-(U10-VBAT-Pad19)") (class "Default")
      (node (ref "U10") (pin "19") (pinfunction "VBAT_19") (pintype "passive"))
    )
    (net (code "97") (name "unconnected-(U10-~{RSTOUT}-Pad14)") (class "Default")
      (node (ref "U10") (pin "14") (pinfunction "~{RSTOUT}_14") (pintype "passive"))
    )
    (net (code "98") (name "unconnected-(U10-~{TRST}-Pad4)") (class "Default")
      (node (ref "U10") (pin "4") (pinfunction "~{TRST}_4") (pintype "passive"))
    )
    (net (code "99") (name "unconnected-(U11-CLK_OUT-Pad25)") (class "Default")
      (node (ref "U11") (pin "25") (pinfunction "CLK_OUT_25") (pintype "passive"))
    )
    (net (code "100") (name "unconnected-(U11-COL{slash}PHYAD0-Pad42)") (class "Default")
      (node (ref "U11") (pin "42") (pinfunction "COL/PHYAD0_42") (pintype "passive"))
    )
    (net (code "101") (name "unconnected-(U11-RXD_2{slash}PHYAD3-Pad45)") (class "Default")
      (node (ref "U11") (pin "45") (pinfunction "RXD_2/PHYAD3_45") (pintype "passive"))
    )
    (net (code "102") (name "unconnected-(U11-RXD_3{slash}PHYAD4-Pad46)") (class "Default")
      (node (ref "U11") (pin "46") (pinfunction "RXD_3/PHYAD4_46") (pintype "passive"))
    )
    (net (code "103") (name "unconnected-(U11-RX_CLK-Pad38)") (class "Default")
      (node (ref "U11") (pin "38") (pinfunction "RX_CLK_38") (pintype "passive"))
    )
    (net (code "104") (name "unconnected-(U11-TCK-Pad8)") (class "Default")
      (node (ref "U11") (pin "8") (pinfunction "TCK_8") (pintype "passive"))
    )
    (net (code "105") (name "unconnected-(U11-TDI-Pad12)") (class "Default")
      (node (ref "U11") (pin "12") (pinfunction "TDI_12") (pintype "passive"))
    )
    (net (code "106") (name "unconnected-(U11-TDO-Pad9)") (class "Default")
      (node (ref "U11") (pin "9") (pinfunction "TDO_9") (pintype "passive"))
    )
    (net (code "107") (name "unconnected-(U11-TMS-Pad10)") (class "Default")
      (node (ref "U11") (pin "10") (pinfunction "TMS_10") (pintype "passive"))
    )
    (net (code "108") (name "unconnected-(U11-TXD_2-Pad5)") (class "Default")
      (node (ref "U11") (pin "5") (pinfunction "TXD_2_5") (pintype "passive"))
    )
    (net (code "109") (name "unconnected-(U11-TXD_3{slash}SNI_MODE-Pad6)") (class "Default")
      (node (ref "U11") (pin "6") (pinfunction "TXD_3/SNI_MODE_6") (pintype "passive"))
    )
    (net (code "110") (name "unconnected-(U11-TX_CLK-Pad1)") (class "Default")
      (node (ref "U11") (pin "1") (pinfunction "TX_CLK_1") (pintype "passive"))
    )
    (net (code "111") (name "unconnected-(U11-X2-Pad33)") (class "Default")
      (node (ref "U11") (pin "33") (pinfunction "X2_33") (pintype "passive"))
    )
    (net (code "112") (name "unconnected-(U11-~{TRST}-Pad11)") (class "Default")
      (node (ref "U11") (pin "11") (pinfunction "~{TRST}_11") (pintype "passive"))
    )
  )
)
